# Qwiic_Iridium_9603N.net
KiCad netlist of a schematic drawn in EAGLE
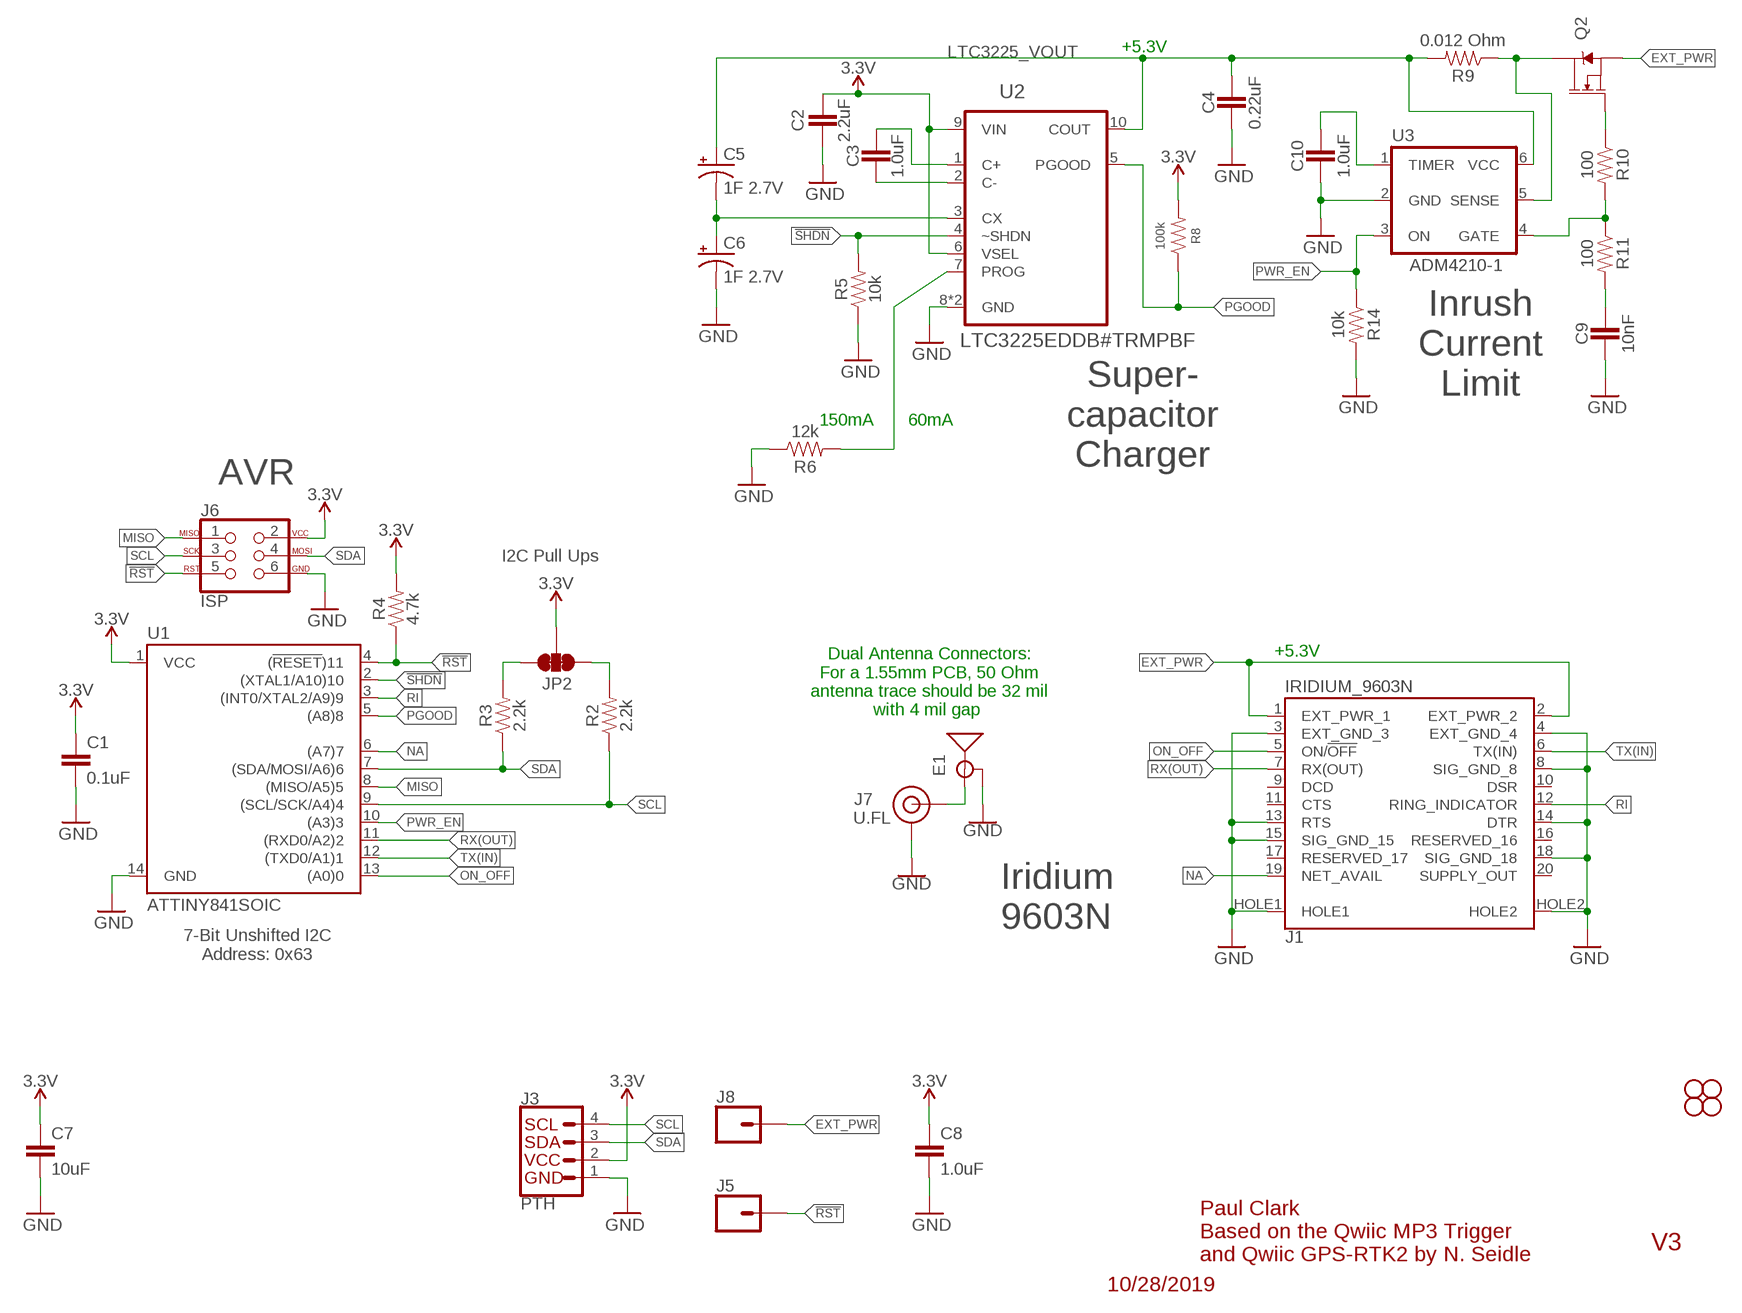
[diagram p0: schematic, sheet 1]

(export (version "E")
  (design (tool "Eeschema 10.0.6"))
  (components
    (comp (ref "C1")
      (value "0.1uF")
      (footprint "eagle-import:0603")
      (libsource (lib "eagle-import") (part "0.1UF-0603-25V-5%"))
    )
    (comp (ref "C2")
      (value "2.2uF")
      (footprint "eagle-import:0603")
      (libsource (lib "eagle-import") (part "2.2UF-0603-10V-20%"))
    )
    (comp (ref "C3")
      (value "1.0uF")
      (footprint "eagle-import:0603")
      (libsource (lib "eagle-import") (part "1.0UF-0603-16V-10%-X7R"))
    )
    (comp (ref "C4")
      (value "0.22uF")
      (footprint "eagle-import:0603")
      (libsource (lib "eagle-import") (part "0.22UF-0603-25V-10%"))
    )
    (comp (ref "C5")
      (value "1F 2.7V")
      (footprint "eagle-import:CPOL-RADIAL-1F-2.7V")
      (libsource (lib "eagle-import") (part "1F-2.7V(PTH)CPOL-RADIAL-1H-2.7V"))
    )
    (comp (ref "C6")
      (value "1F 2.7V")
      (footprint "eagle-import:CPOL-RADIAL-1F-2.7V")
      (libsource (lib "eagle-import") (part "1F-2.7V(PTH)CPOL-RADIAL-1H-2.7V"))
    )
    (comp (ref "C7")
      (value "10uF")
      (footprint "eagle-import:0603")
      (libsource (lib "eagle-import") (part "10UF-0603-6.3V-20%"))
    )
    (comp (ref "C8")
      (value "1.0uF")
      (footprint "eagle-import:0603")
      (libsource (lib "eagle-import") (part "1.0UF-0603-16V-10%-X7R"))
    )
    (comp (ref "C9")
      (value "10nF")
      (footprint "eagle-import:0603")
      (libsource (lib "eagle-import") (part "10NF-0603-50V-10%"))
    )
    (comp (ref "C10")
      (value "1.0uF")
      (footprint "eagle-import:0603")
      (libsource (lib "eagle-import") (part "1.0UF-0603-16V-10%-X7R"))
    )
    (comp (ref "E1")
      (value "ANTENNA-GROUNDEDEDGE_SMA")
      (footprint "eagle-import:SMA-EDGE")
      (libsource (lib "eagle-import") (part "ANTENNA-GROUNDEDEDGE_SMA"))
    )
    (comp (ref "J1")
      (value "IRIDIUM_9603N")
      (footprint "eagle-import:IRIDIUM_9603N")
      (libsource (lib "eagle-import") (part "IRIDIUM_9603N"))
    )
    (comp (ref "J3")
      (value "PTH")
      (footprint "eagle-import:1X04_1MM_RA")
      (libsource (lib "eagle-import") (part "I2C_STANDARDJS-1MM"))
    )
    (comp (ref "J5")
      (value "CONN_01PTH_NO_SILK_YES_STOP")
      (footprint "eagle-import:1X01_NO_SILK")
      (libsource (lib "eagle-import") (part "CONN_01PTH_NO_SILK_YES_STOP"))
    )
    (comp (ref "J6")
      (value "ISP")
      (footprint "eagle-import:2X3_TEST_POINTS")
      (libsource (lib "eagle-import") (part "AVR_SPI_PROG_3X2TESTPOINTS"))
    )
    (comp (ref "J7")
      (value "U.FL")
      (footprint "eagle-import:U.FL")
      (libsource (lib "eagle-import") (part "U.FL2PIN"))
    )
    (comp (ref "J8")
      (value "CONN_01PTH_NO_SILK_YES_STOP")
      (footprint "eagle-import:1X01_NO_SILK")
      (libsource (lib "eagle-import") (part "CONN_01PTH_NO_SILK_YES_STOP"))
    )
    (comp (ref "JP2")
      (value "JUMPER-SMT_3_2-NC_TRACE_SILK")
      (footprint "eagle-import:SMT-JUMPER_3_2-NC_TRACE_SILK")
      (libsource (lib "eagle-import") (part "JUMPER-SMT_3_2-NC_TRACE_SILK"))
    )
    (comp (ref "JP3")
      (value "STAND-OFF")
      (footprint "eagle-import:STAND-OFF")
      (libsource (lib "eagle-import") (part "STAND-OFF"))
    )
    (comp (ref "JP4")
      (value "STAND-OFF")
      (footprint "eagle-import:STAND-OFF")
      (libsource (lib "eagle-import") (part "STAND-OFF"))
    )
    (comp (ref "JP9")
      (value "STAND-OFF")
      (footprint "eagle-import:STAND-OFF")
      (libsource (lib "eagle-import") (part "STAND-OFF"))
    )
    (comp (ref "JP10")
      (value "STAND-OFF")
      (footprint "eagle-import:STAND-OFF")
      (libsource (lib "eagle-import") (part "STAND-OFF"))
    )
    (comp (ref "Q2")
      (value "5.8A/30V/35mΩ")
      (footprint "eagle-import:SOT23-3")
      (libsource (lib "eagle-import") (part "MOSFET-NCH-AO3404A"))
    )
    (comp (ref "R2")
      (value "2.2k")
      (footprint "eagle-import:0603")
      (libsource (lib "eagle-import") (part "2.2KOHM-0603-1/10W-1%"))
    )
    (comp (ref "R3")
      (value "2.2k")
      (footprint "eagle-import:0603")
      (libsource (lib "eagle-import") (part "2.2KOHM-0603-1/10W-1%"))
    )
    (comp (ref "R4")
      (value "4.7k")
      (footprint "eagle-import:0603")
      (libsource (lib "eagle-import") (part "4.7KOHM-0603-1/10W-1%"))
    )
    (comp (ref "R5")
      (value "10k")
      (footprint "eagle-import:0603")
      (libsource (lib "eagle-import") (part "10KOHM-0603-1/10W-1%"))
    )
    (comp (ref "R6")
      (value "12k")
      (footprint "eagle-import:0603")
      (libsource (lib "eagle-import") (part "12KOHM-0603-1/10W-1%"))
    )
    (comp (ref "R8")
      (value "100k")
      (footprint "eagle-import:0603")
      (libsource (lib "eagle-import") (part "100KOHM-0603-1/10W-1%"))
    )
    (comp (ref "R9")
      (value "0.012 Ohm")
      (footprint "eagle-import:0603")
      (libsource (lib "eagle-import") (part "RESISTOR0603"))
    )
    (comp (ref "R10")
      (value "100")
      (footprint "eagle-import:0603")
      (libsource (lib "eagle-import") (part "100OHM-0603-1/10W-1%"))
    )
    (comp (ref "R11")
      (value "100")
      (footprint "eagle-import:0603")
      (libsource (lib "eagle-import") (part "100OHM-0603-1/10W-1%"))
    )
    (comp (ref "R14")
      (value "10k")
      (footprint "eagle-import:0603")
      (libsource (lib "eagle-import") (part "SparkFun-Resistors_532_10KOHM-0603-1/10W-1%"))
    )
    (comp (ref "U1")
      (value "ATTINY841SOIC")
      (footprint "eagle-import:ATTINY841")
      (libsource (lib "eagle-import") (part "ATTINY841SOIC"))
    )
    (comp (ref "U2")
      (value "LTC3225EDDB#TRMPBF")
      (footprint "eagle-import:DFN300X200-10L")
      (libsource (lib "eagle-import") (part "LTC3225EDDB-TRMPBFDFN300X200-10L"))
    )
    (comp (ref "U3")
      (value "ADM4210-1")
      (footprint "eagle-import:TSOT6")
      (libsource (lib "eagle-import") (part "ADM4210-1"))
    )
  )
  (nets
    (net (code "1") (name "/LTC3225_VOUT") (class "Default")
      (node (ref "C4") (pin "1") (pinfunction "1_1") (pintype "passive"))
      (node (ref "C5") (pin "+") (pinfunction "+_+") (pintype "passive"))
      (node (ref "R9") (pin "2") (pinfunction "2_2") (pintype "passive"))
      (node (ref "U2") (pin "10") (pinfunction "COUT_10") (pintype "output"))
      (node (ref "U3") (pin "6") (pinfunction "VCC_6") (pintype "power_in"))
    )
    (net (code "2") (name "/~{RST}") (class "Default")
      (node (ref "J5") (pin "1") (pinfunction "1_1") (pintype "passive"))
      (node (ref "J6") (pin "5") (pinfunction "5_5") (pintype "passive"))
      (node (ref "R4") (pin "1") (pinfunction "1_1") (pintype "passive"))
      (node (ref "U1") (pin "4") (pinfunction "(~{RESET})11_4") (pintype "bidirectional"))
    )
    (net (code "3") (name "/~{SHDN}") (class "Default")
      (node (ref "R5") (pin "2") (pinfunction "2_2") (pintype "passive"))
      (node (ref "U1") (pin "2") (pinfunction "(XTAL1/A10)10_2") (pintype "bidirectional"))
      (node (ref "U2") (pin "4") (pinfunction "~{SHDN}_4") (pintype "input"))
    )
    (net (code "4") (name "3.3V") (class "Default")
      (node (ref "C1") (pin "1") (pinfunction "1_1") (pintype "passive"))
      (node (ref "C2") (pin "1") (pinfunction "1_1") (pintype "passive"))
      (node (ref "C7") (pin "1") (pinfunction "1_1") (pintype "passive"))
      (node (ref "C8") (pin "1") (pinfunction "1_1") (pintype "passive"))
      (node (ref "J3") (pin "2") (pinfunction "VCC_2") (pintype "power_in"))
      (node (ref "J6") (pin "2") (pinfunction "2_2") (pintype "passive"))
      (node (ref "JP2") (pin "2") (pinfunction "2_2") (pintype "passive"))
      (node (ref "R4") (pin "2") (pinfunction "2_2") (pintype "passive"))
      (node (ref "R8") (pin "2") (pinfunction "2_2") (pintype "passive"))
      (node (ref "U1") (pin "1") (pinfunction "VCC_1") (pintype "bidirectional"))
      (node (ref "U2") (pin "6") (pinfunction "VSEL_6") (pintype "input"))
      (node (ref "U2") (pin "9") (pinfunction "VIN_9") (pintype "power_in"))
    )
    (net (code "5") (name "EXT_PWR") (class "Default")
      (node (ref "J1") (pin "1") (pinfunction "EXT_PWR_1_1") (pintype "power_in"))
      (node (ref "J1") (pin "2") (pinfunction "EXT_PWR_2_2") (pintype "power_in"))
      (node (ref "J8") (pin "1") (pinfunction "1_1") (pintype "passive"))
      (node (ref "Q2") (pin "2") (pinfunction "S_2") (pintype "bidirectional"))
    )
    (net (code "6") (name "GND") (class "Default")
      (node (ref "C1") (pin "2") (pinfunction "2_2") (pintype "passive"))
      (node (ref "C10") (pin "2") (pinfunction "2_2") (pintype "passive"))
      (node (ref "C2") (pin "2") (pinfunction "2_2") (pintype "passive"))
      (node (ref "C4") (pin "2") (pinfunction "2_2") (pintype "passive"))
      (node (ref "C6") (pin "-") (pinfunction "-_-") (pintype "passive"))
      (node (ref "C7") (pin "2") (pinfunction "2_2") (pintype "passive"))
      (node (ref "C8") (pin "2") (pinfunction "2_2") (pintype "passive"))
      (node (ref "C9") (pin "2") (pinfunction "2_2") (pintype "passive"))
      (node (ref "E1") (pin "GND@0") (pinfunction "GND_GND@0") (pintype "bidirectional"))
      (node (ref "E1") (pin "GND@1") (pinfunction "GND_GND@1") (pintype "bidirectional"))
      (node (ref "E1") (pin "GND@2") (pinfunction "GND_GND@2") (pintype "bidirectional"))
      (node (ref "E1") (pin "GND@3") (pinfunction "GND_GND@3") (pintype "bidirectional"))
      (node (ref "J1") (pin "13") (pinfunction "RTS_13") (pintype "input"))
      (node (ref "J1") (pin "14") (pinfunction "DTR_14") (pintype "input"))
      (node (ref "J1") (pin "15") (pinfunction "SIG_GND_15_15") (pintype "power_in"))
      (node (ref "J1") (pin "18") (pinfunction "SIG_GND_18_18") (pintype "power_in"))
      (node (ref "J1") (pin "3") (pinfunction "EXT_GND_3_3") (pintype "power_in"))
      (node (ref "J1") (pin "4") (pinfunction "EXT_GND_4_4") (pintype "power_in"))
      (node (ref "J1") (pin "8") (pinfunction "SIG_GND_8_8") (pintype "power_in"))
      (node (ref "J1") (pin "HOLE1") (pinfunction "HOLE1_HOLE1") (pintype "power_in"))
      (node (ref "J1") (pin "HOLE2") (pinfunction "HOLE2_HOLE2") (pintype "power_in"))
      (node (ref "J3") (pin "1") (pinfunction "GND_1") (pintype "power_in"))
      (node (ref "J6") (pin "6") (pinfunction "6_6") (pintype "passive"))
      (node (ref "J7") (pin "1") (pinfunction "GND_1") (pintype "bidirectional"))
      (node (ref "J7") (pin "2") (pinfunction "GND_2") (pintype "bidirectional"))
      (node (ref "R14") (pin "2") (pinfunction "2_2") (pintype "passive"))
      (node (ref "R5") (pin "1") (pinfunction "1_1") (pintype "passive"))
      (node (ref "R6") (pin "1") (pinfunction "1_1") (pintype "passive"))
      (node (ref "U1") (pin "14") (pinfunction "GND_14") (pintype "bidirectional"))
      (node (ref "U2") (pin "11") (pinfunction "GND_11") (pintype "passive"))
      (node (ref "U2") (pin "8") (pinfunction "GND_8") (pintype "passive"))
      (node (ref "U3") (pin "2") (pinfunction "GND_2") (pintype "power_in"))
    )
    (net (code "7") (name "MISO") (class "Default")
      (node (ref "J6") (pin "1") (pinfunction "1_1") (pintype "passive"))
      (node (ref "U1") (pin "8") (pinfunction "(MISO/A5)5_8") (pintype "bidirectional"))
    )
    (net (code "8") (name "NA") (class "Default")
      (node (ref "J1") (pin "19") (pinfunction "NET_AVAIL_19") (pintype "output"))
      (node (ref "U1") (pin "6") (pinfunction "(A7)7_6") (pintype "bidirectional"))
    )
    (net (code "9") (name "Net-(C9-Pad1)") (class "Default")
      (node (ref "C9") (pin "1") (pinfunction "1_1") (pintype "passive"))
      (node (ref "R11") (pin "2") (pinfunction "2_2") (pintype "passive"))
    )
    (net (code "10") (name "Net-(E1-SIGNAL)") (class "Default")
      (node (ref "E1") (pin "SIG") (pinfunction "SIGNAL_SIG") (pintype "bidirectional"))
      (node (ref "J7") (pin "FEED") (pinfunction "SIGNAL_FEED") (pintype "bidirectional"))
    )
    (net (code "11") (name "Net-(JP2-Pad1)") (class "Default")
      (node (ref "JP2") (pin "1") (pinfunction "1_1") (pintype "passive"))
      (node (ref "R2") (pin "2") (pinfunction "2_2") (pintype "passive"))
    )
    (net (code "12") (name "Net-(JP2-Pad3)") (class "Default")
      (node (ref "JP2") (pin "3") (pinfunction "3_3") (pintype "passive"))
      (node (ref "R3") (pin "2") (pinfunction "2_2") (pintype "passive"))
    )
    (net (code "13") (name "Net-(Q2-D)") (class "Default")
      (node (ref "Q2") (pin "3") (pinfunction "D_3") (pintype "bidirectional"))
      (node (ref "R9") (pin "1") (pinfunction "1_1") (pintype "passive"))
      (node (ref "U3") (pin "5") (pinfunction "SENSE_5") (pintype "input"))
    )
    (net (code "14") (name "Net-(Q2-G)") (class "Default")
      (node (ref "Q2") (pin "1") (pinfunction "G_1") (pintype "bidirectional"))
      (node (ref "R10") (pin "1") (pinfunction "1_1") (pintype "passive"))
    )
    (net (code "15") (name "Net-(U2-C+)") (class "Default")
      (node (ref "C3") (pin "1") (pinfunction "1_1") (pintype "passive"))
      (node (ref "U2") (pin "1") (pinfunction "C+_1") (pintype "passive"))
    )
    (net (code "16") (name "Net-(U2-C-)") (class "Default")
      (node (ref "C3") (pin "2") (pinfunction "2_2") (pintype "passive"))
      (node (ref "U2") (pin "2") (pinfunction "C-_2") (pintype "passive"))
    )
    (net (code "17") (name "Net-(U2-CX)") (class "Default")
      (node (ref "C5") (pin "-") (pinfunction "-_-") (pintype "passive"))
      (node (ref "C6") (pin "+") (pinfunction "+_+") (pintype "passive"))
      (node (ref "U2") (pin "3") (pinfunction "CX_3") (pintype "passive"))
    )
    (net (code "18") (name "Net-(U2-PROG)") (class "Default")
      (node (ref "R6") (pin "2") (pinfunction "2_2") (pintype "passive"))
      (node (ref "U2") (pin "7") (pinfunction "PROG_7") (pintype "input"))
    )
    (net (code "19") (name "Net-(U3-GATE)") (class "Default")
      (node (ref "R10") (pin "2") (pinfunction "2_2") (pintype "passive"))
      (node (ref "R11") (pin "1") (pinfunction "1_1") (pintype "passive"))
      (node (ref "U3") (pin "4") (pinfunction "GATE_4") (pintype "output"))
    )
    (net (code "20") (name "Net-(U3-TIMER)") (class "Default")
      (node (ref "C10") (pin "1") (pinfunction "1_1") (pintype "passive"))
      (node (ref "U3") (pin "1") (pinfunction "TIMER_1") (pintype "input"))
    )
    (net (code "21") (name "ON_OFF") (class "Default")
      (node (ref "J1") (pin "5") (pinfunction "ON/~{OFF}_5") (pintype "input"))
      (node (ref "U1") (pin "13") (pinfunction "(A0)0_13") (pintype "bidirectional"))
    )
    (net (code "22") (name "PGOOD") (class "Default")
      (node (ref "R8") (pin "1") (pinfunction "1_1") (pintype "passive"))
      (node (ref "U1") (pin "5") (pinfunction "(A8)8_5") (pintype "bidirectional"))
      (node (ref "U2") (pin "5") (pinfunction "PGOOD_5") (pintype "output"))
    )
    (net (code "23") (name "PWR_EN") (class "Default")
      (node (ref "R14") (pin "1") (pinfunction "1_1") (pintype "passive"))
      (node (ref "U1") (pin "10") (pinfunction "(A3)3_10") (pintype "bidirectional"))
      (node (ref "U3") (pin "3") (pinfunction "ON_3") (pintype "input"))
    )
    (net (code "24") (name "RI") (class "Default")
      (node (ref "J1") (pin "12") (pinfunction "RING_INDICATOR_12") (pintype "output"))
      (node (ref "U1") (pin "3") (pinfunction "(INT0/XTAL2/A9)9_3") (pintype "bidirectional"))
    )
    (net (code "25") (name "RX(OUT)") (class "Default")
      (node (ref "J1") (pin "7") (pinfunction "RX(OUT)_7") (pintype "output"))
      (node (ref "U1") (pin "11") (pinfunction "(RXD0/A2)2_11") (pintype "bidirectional"))
    )
    (net (code "26") (name "SCL") (class "Default")
      (node (ref "J3") (pin "4") (pinfunction "SCL_4") (pintype "passive"))
      (node (ref "J6") (pin "3") (pinfunction "3_3") (pintype "passive"))
      (node (ref "R2") (pin "1") (pinfunction "1_1") (pintype "passive"))
      (node (ref "U1") (pin "9") (pinfunction "(SCL/SCK/A4)4_9") (pintype "bidirectional"))
    )
    (net (code "27") (name "SDA") (class "Default")
      (node (ref "J3") (pin "3") (pinfunction "SDA_3") (pintype "passive"))
      (node (ref "J6") (pin "4") (pinfunction "4_4") (pintype "passive"))
      (node (ref "R3") (pin "1") (pinfunction "1_1") (pintype "passive"))
      (node (ref "U1") (pin "7") (pinfunction "(SDA/MOSI/A6)6_7") (pintype "bidirectional"))
    )
    (net (code "28") (name "TX(IN)") (class "Default")
      (node (ref "J1") (pin "6") (pinfunction "TX(IN)_6") (pintype "input"))
      (node (ref "U1") (pin "12") (pinfunction "(TXD0/A1)1_12") (pintype "bidirectional"))
    )
    (net (code "29") (name "unconnected-(J1-CTS-Pad11)") (class "Default")
      (node (ref "J1") (pin "11") (pinfunction "CTS_11") (pintype "output"))
    )
    (net (code "30") (name "unconnected-(J1-DCD-Pad9)") (class "Default")
      (node (ref "J1") (pin "9") (pinfunction "DCD_9") (pintype "output"))
    )
    (net (code "31") (name "unconnected-(J1-DSR-Pad10)") (class "Default")
      (node (ref "J1") (pin "10") (pinfunction "DSR_10") (pintype "output"))
    )
    (net (code "32") (name "unconnected-(J1-RESERVED_16-Pad16)") (class "Default")
      (node (ref "J1") (pin "16") (pinfunction "RESERVED_16_16") (pintype "no_connect"))
    )
    (net (code "33") (name "unconnected-(J1-RESERVED_17-Pad17)") (class "Default")
      (node (ref "J1") (pin "17") (pinfunction "RESERVED_17_17") (pintype "no_connect"))
    )
    (net (code "34") (name "unconnected-(J1-SUPPLY_OUT-Pad20)") (class "Default")
      (node (ref "J1") (pin "20") (pinfunction "SUPPLY_OUT_20") (pintype "output"))
    )
  )
)
